# fx3_a.net
KiCad netlist of a schematic drawn in Altium Designer
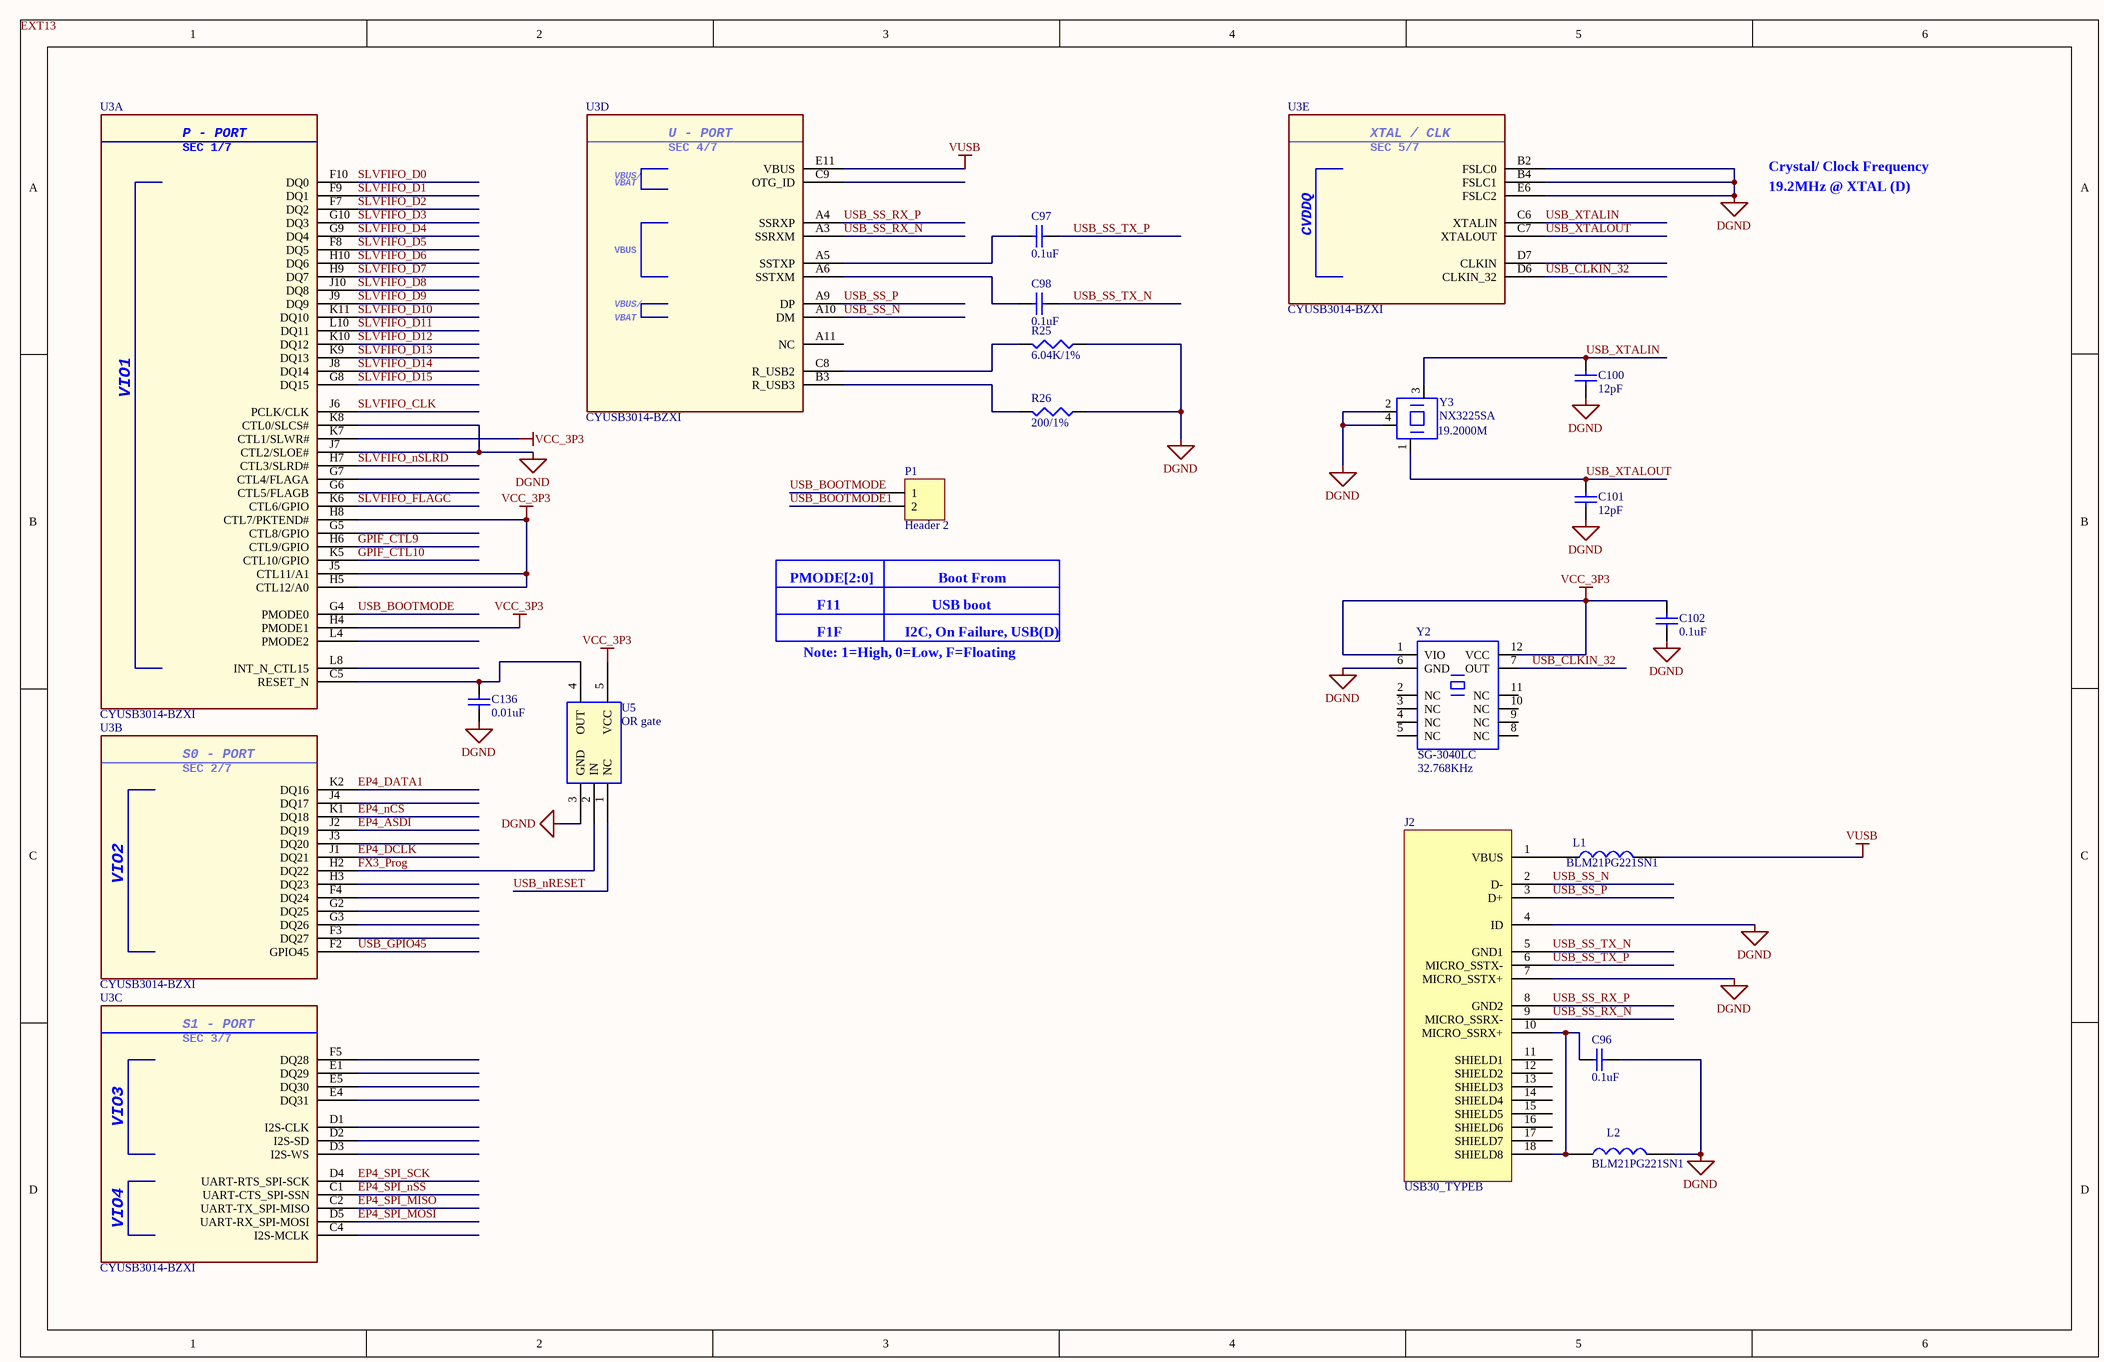
[diagram p0: fx3_a.SchDoc]

(export (version "E")
  (design (tool "Eeschema 10.0.6"))
  (components
    (comp (ref "C96")
      (value "0.1uF")
      (footprint "C_0402")
      (description "Capacitor (Semiconductor SIM Model)")
      (fields (field (name "Comment") "Capacitor") (field (name "PUBLISHER") "Altium Limited"))
      (libsource (lib "Miscellaneous Devices") (part "Cap Semi"))
    )
    (comp (ref "C97")
      (value "0.1uF")
      (footprint "C_0402")
      (description "Capacitor (Semiconductor SIM Model)")
      (fields (field (name "Comment") "Capacitor") (field (name "PUBLISHER") "Altium Limited"))
      (libsource (lib "Miscellaneous Devices") (part "Cap Semi"))
    )
    (comp (ref "C98")
      (value "0.1uF")
      (footprint "C_0402")
      (description "Capacitor (Semiconductor SIM Model)")
      (fields (field (name "Comment") "Capacitor") (field (name "PUBLISHER") "Altium Limited"))
      (libsource (lib "Miscellaneous Devices") (part "Cap Semi"))
    )
    (comp (ref "C100")
      (value "12pF")
      (footprint "C_0402")
      (description "Capacitor (Semiconductor SIM Model)")
      (fields (field (name "Comment") "Capacitor") (field (name "PUBLISHER") "Altium Limited"))
      (libsource (lib "Miscellaneous Devices") (part "Cap Semi"))
    )
    (comp (ref "C101")
      (value "12pF")
      (footprint "C_0402")
      (description "Capacitor (Semiconductor SIM Model)")
      (fields (field (name "Comment") "Capacitor") (field (name "PUBLISHER") "Altium Limited"))
      (libsource (lib "Miscellaneous Devices") (part "Cap Semi"))
    )
    (comp (ref "C102")
      (value "0.1uF")
      (footprint "C_0402")
      (description "Capacitor (Semiconductor SIM Model)")
      (fields (field (name "Comment") "Capacitor") (field (name "PUBLISHER") "Altium Limited"))
      (libsource (lib "Miscellaneous Devices") (part "Cap Semi"))
    )
    (comp (ref "C136")
      (value "0.01uF")
      (footprint "C_0402")
      (description "Capacitor (Semiconductor SIM Model)")
      (fields (field (name "Comment") "Capacitor") (field (name "PUBLISHER") "Altium Limited"))
      (libsource (lib "Miscellaneous Devices") (part "Cap Semi"))
    )
    (comp (ref "J2")
      (value "USB30_TYPEB")
      (footprint "USB3.0 typeB")
      (description "USB30_MICRO_TYPEB")
      (libsource (lib "apex_usb_v2") (part "USB30_TYPEB"))
    )
    (comp (ref "L1")
      (value "BLM21PG221SN1")
      (footprint "SMD_0805")
      (description "Chip Ferrite Bead")
      (libsource (lib "apex_usb_v2") (part "BLM21PXXX"))
    )
    (comp (ref "L2")
      (value "BLM21PG221SN1")
      (footprint "SMD_0805")
      (description "Chip Ferrite Bead")
      (libsource (lib "apex_usb_v2") (part "BLM21PXXX"))
    )
    (comp (ref "P1")
      (value "Header 2")
      (footprint "HDR1X2")
      (description "Header, 2-Pin")
      (fields (field (name "PUBLISHER") "Altium Limited"))
      (libsource (lib "Miscellaneous Connectors") (part "Header 2"))
    )
    (comp (ref "R25")
      (value "6.04K/1%")
      (footprint "J1-0603")
      (description "Resistor")
      (fields (field (name "PUBLISHER") "Altium Limited"))
      (libsource (lib "Miscellaneous Devices") (part "Res3"))
    )
    (comp (ref "R26")
      (value "200/1%")
      (footprint "J1-0603")
      (description "Resistor")
      (fields (field (name "PUBLISHER") "Altium Limited"))
      (libsource (lib "Miscellaneous Devices") (part "Res3"))
    )
    (comp (ref "U3")
      (value "CYUSB3014-BZXI")
      (footprint "CYP-BZX121")
      (description "FX3 CYUSB3014")
      (libsource (lib "apex_usb_v2") (part "CYUSB30XX"))
    )
    (comp (ref "U5")
      (value "OR gate")
      (footprint "TC7SET08FU")
      (libsource (lib "auxiliarylib1") (part "INVERTER"))
    )
    (comp (ref "Y2")
      (value "SG-3040LC")
      (footprint "SG-3040LC")
      (description "CRYSTAL")
      (fields (field (name "ALTIUM_VALUE") "32.768KHz"))
      (libsource (lib "apex_usb_v2") (part "SG3040"))
    )
    (comp (ref "Y3")
      (value "NX3225SA")
      (footprint "CRYSTAL_SMD_32X25")
      (description "CRYSTAL")
      (fields (field (name "ALTIUM_VALUE") "19.2000M"))
      (libsource (lib "clc_ad_pro") (part "NX3225SA"))
    )
  )
  (nets
    (net (code "1") (name "/EP4_ASDI") (class "Default")
      (node (ref "U3") (pin "J2") (pinfunction "DQ19_J2") (pintype "passive"))
    )
    (net (code "2") (name "/EP4_DATA1") (class "Default")
      (node (ref "U3") (pin "K2") (pinfunction "DQ16_K2") (pintype "passive"))
    )
    (net (code "3") (name "/EP4_DCLK") (class "Default")
      (node (ref "U3") (pin "J1") (pinfunction "DQ21_J1") (pintype "passive"))
    )
    (net (code "4") (name "/EP4_SPI_MISO") (class "Default")
      (node (ref "U3") (pin "C2") (pinfunction "UART-TX_SPI-MISO_C2") (pintype "passive"))
    )
    (net (code "5") (name "/EP4_SPI_MOSI") (class "Default")
      (node (ref "U3") (pin "D5") (pinfunction "UART-RX_SPI-MOSI_D5") (pintype "passive"))
    )
    (net (code "6") (name "/EP4_SPI_SCK") (class "Default")
      (node (ref "U3") (pin "D4") (pinfunction "UART-RTS_SPI-SCK_D4") (pintype "passive"))
    )
    (net (code "7") (name "/EP4_SPI_nSS") (class "Default")
      (node (ref "U3") (pin "C1") (pinfunction "UART-CTS_SPI-SSN_C1") (pintype "passive"))
    )
    (net (code "8") (name "/EP4_nCS") (class "Default")
      (node (ref "U3") (pin "K1") (pinfunction "DQ18_K1") (pintype "passive"))
    )
    (net (code "10") (name "/FX3_Prog") (class "Default")
      (node (ref "U3") (pin "H2") (pinfunction "DQ22_H2") (pintype "passive"))
      (node (ref "U5") (pin "2") (pinfunction "IN_2") (pintype "passive"))
    )
    (net (code "11") (name "/GPIF_CTL9") (class "Default")
      (node (ref "U3") (pin "H6") (pinfunction "CTL9/GPIO_H6") (pintype "passive"))
    )
    (net (code "12") (name "/GPIF_CTL10") (class "Default")
      (node (ref "U3") (pin "K5") (pinfunction "CTL10/GPIO_K5") (pintype "passive"))
    )
    (net (code "13") (name "/SLVFIFO_CLK") (class "Default")
      (node (ref "U3") (pin "J6") (pinfunction "PCLK/CLK_J6") (pintype "passive"))
    )
    (net (code "14") (name "/SLVFIFO_D0") (class "Default")
      (node (ref "U3") (pin "F10") (pinfunction "DQ0_F10") (pintype "passive"))
    )
    (net (code "15") (name "/SLVFIFO_D1") (class "Default")
      (node (ref "U3") (pin "F9") (pinfunction "DQ1_F9") (pintype "passive"))
    )
    (net (code "16") (name "/SLVFIFO_D2") (class "Default")
      (node (ref "U3") (pin "F7") (pinfunction "DQ2_F7") (pintype "passive"))
    )
    (net (code "17") (name "/SLVFIFO_D3") (class "Default")
      (node (ref "U3") (pin "G10") (pinfunction "DQ3_G10") (pintype "passive"))
    )
    (net (code "18") (name "/SLVFIFO_D4") (class "Default")
      (node (ref "U3") (pin "G9") (pinfunction "DQ4_G9") (pintype "passive"))
    )
    (net (code "19") (name "/SLVFIFO_D5") (class "Default")
      (node (ref "U3") (pin "F8") (pinfunction "DQ5_F8") (pintype "passive"))
    )
    (net (code "20") (name "/SLVFIFO_D6") (class "Default")
      (node (ref "U3") (pin "H10") (pinfunction "DQ6_H10") (pintype "passive"))
    )
    (net (code "21") (name "/SLVFIFO_D7") (class "Default")
      (node (ref "U3") (pin "H9") (pinfunction "DQ7_H9") (pintype "passive"))
    )
    (net (code "22") (name "/SLVFIFO_D8") (class "Default")
      (node (ref "U3") (pin "J10") (pinfunction "DQ8_J10") (pintype "passive"))
    )
    (net (code "23") (name "/SLVFIFO_D9") (class "Default")
      (node (ref "U3") (pin "J9") (pinfunction "DQ9_J9") (pintype "passive"))
    )
    (net (code "24") (name "/SLVFIFO_D10") (class "Default")
      (node (ref "U3") (pin "K11") (pinfunction "DQ10_K11") (pintype "passive"))
    )
    (net (code "25") (name "/SLVFIFO_D11") (class "Default")
      (node (ref "U3") (pin "L10") (pinfunction "DQ11_L10") (pintype "passive"))
    )
    (net (code "26") (name "/SLVFIFO_D12") (class "Default")
      (node (ref "U3") (pin "K10") (pinfunction "DQ12_K10") (pintype "passive"))
    )
    (net (code "27") (name "/SLVFIFO_D13") (class "Default")
      (node (ref "U3") (pin "K9") (pinfunction "DQ13_K9") (pintype "passive"))
    )
    (net (code "28") (name "/SLVFIFO_D14") (class "Default")
      (node (ref "U3") (pin "J8") (pinfunction "DQ14_J8") (pintype "passive"))
    )
    (net (code "29") (name "/SLVFIFO_D15") (class "Default")
      (node (ref "U3") (pin "G8") (pinfunction "DQ15_G8") (pintype "passive"))
    )
    (net (code "30") (name "/SLVFIFO_FLAGC") (class "Default")
      (node (ref "U3") (pin "K6") (pinfunction "CTL6/GPIO_K6") (pintype "passive"))
    )
    (net (code "31") (name "/SLVFIFO_nSLRD") (class "Default")
      (node (ref "U3") (pin "H7") (pinfunction "CTL3/SLRD#_H7") (pintype "passive"))
    )
    (net (code "32") (name "/USB_BOOTMODE") (class "Default")
      (node (ref "P1") (pin "1") (pinfunction "1_1") (pintype "passive"))
      (node (ref "U3") (pin "G4") (pinfunction "PMODE0_G4") (pintype "passive"))
    )
    (net (code "33") (name "/USB_BOOTMODE1") (class "Default")
      (node (ref "P1") (pin "2") (pinfunction "2_2") (pintype "passive"))
    )
    (net (code "34") (name "/USB_CLKIN_32") (class "Default")
      (node (ref "U3") (pin "D6") (pinfunction "CLKIN_32_D6") (pintype "passive"))
      (node (ref "Y2") (pin "7") (pinfunction "OUT_7") (pintype "passive"))
    )
    (net (code "35") (name "/USB_GPIO45") (class "Default")
      (node (ref "U3") (pin "F2") (pinfunction "GPIO45_F2") (pintype "passive"))
    )
    (net (code "36") (name "/USB_SS_N") (class "Default")
      (node (ref "J2") (pin "2") (pinfunction "D-_2") (pintype "passive"))
      (node (ref "U3") (pin "A10") (pinfunction "DM_A10") (pintype "passive"))
    )
    (net (code "37") (name "/USB_SS_P") (class "Default")
      (node (ref "J2") (pin "3") (pinfunction "D+_3") (pintype "passive"))
      (node (ref "U3") (pin "A9") (pinfunction "DP_A9") (pintype "passive"))
    )
    (net (code "38") (name "/USB_SS_RX_N") (class "Default")
      (node (ref "J2") (pin "9") (pinfunction "MICRO_SSRX-_9") (pintype "passive"))
      (node (ref "U3") (pin "A3") (pinfunction "SSRXM_A3") (pintype "passive"))
    )
    (net (code "39") (name "/USB_SS_RX_P") (class "Default")
      (node (ref "J2") (pin "8") (pinfunction "GND2_8") (pintype "passive"))
      (node (ref "U3") (pin "A4") (pinfunction "SSRXP_A4") (pintype "passive"))
    )
    (net (code "40") (name "/USB_SS_TX_N") (class "Default")
      (node (ref "C98") (pin "2") (pinfunction "2_2") (pintype "passive"))
      (node (ref "J2") (pin "5") (pinfunction "GND1_5") (pintype "passive"))
    )
    (net (code "41") (name "/USB_SS_TX_P") (class "Default")
      (node (ref "C97") (pin "2") (pinfunction "2_2") (pintype "passive"))
      (node (ref "J2") (pin "6") (pinfunction "MICRO_SSTX-_6") (pintype "passive"))
    )
    (net (code "42") (name "/USB_XTALIN") (class "Default")
      (node (ref "C100") (pin "2") (pinfunction "2_2") (pintype "passive"))
      (node (ref "U3") (pin "C6") (pinfunction "XTALIN_C6") (pintype "passive"))
      (node (ref "Y3") (pin "3") (pinfunction "3_3") (pintype "passive"))
    )
    (net (code "43") (name "/USB_XTALOUT") (class "Default")
      (node (ref "C101") (pin "2") (pinfunction "2_2") (pintype "passive"))
      (node (ref "U3") (pin "C7") (pinfunction "XTALOUT_C7") (pintype "passive"))
      (node (ref "Y3") (pin "1") (pinfunction "1_1") (pintype "passive"))
    )
    (net (code "44") (name "/USB_nRESET") (class "Default")
      (node (ref "U5") (pin "1") (pinfunction "NC_1") (pintype "passive"))
    )
    (net (code "45") (name "DGND") (class "Default")
      (node (ref "C100") (pin "1") (pinfunction "1_1") (pintype "passive"))
      (node (ref "C101") (pin "1") (pinfunction "1_1") (pintype "passive"))
      (node (ref "C102") (pin "1") (pinfunction "1_1") (pintype "passive"))
      (node (ref "C136") (pin "2") (pinfunction "2_2") (pintype "passive"))
      (node (ref "C96") (pin "2") (pinfunction "2_2") (pintype "passive"))
      (node (ref "J2") (pin "4") (pinfunction "ID_4") (pintype "passive"))
      (node (ref "J2") (pin "7") (pinfunction "MICRO_SSTX+_7") (pintype "passive"))
      (node (ref "L2") (pin "2") (pinfunction "2_2") (pintype "passive"))
      (node (ref "R25") (pin "1") (pinfunction "1_1") (pintype "passive"))
      (node (ref "R26") (pin "1") (pinfunction "1_1") (pintype "passive"))
      (node (ref "U3") (pin "B2") (pinfunction "FSLC0_B2") (pintype "passive"))
      (node (ref "U3") (pin "B4") (pinfunction "FSLC1_B4") (pintype "passive"))
      (node (ref "U3") (pin "E6") (pinfunction "FSLC2_E6") (pintype "passive"))
      (node (ref "U3") (pin "J7") (pinfunction "CTL2/SLOE#_J7") (pintype "passive"))
      (node (ref "U3") (pin "K8") (pinfunction "CTL0/SLCS#_K8") (pintype "passive"))
      (node (ref "U5") (pin "3") (pinfunction "GND_3") (pintype "passive"))
      (node (ref "Y2") (pin "6") (pinfunction "GND_6") (pintype "passive"))
      (node (ref "Y3") (pin "2") (pinfunction "2_2") (pintype "passive"))
      (node (ref "Y3") (pin "4") (pinfunction "4_4") (pintype "passive"))
    )
    (net (code "46") (name "Net-(J2-MICRO_SSRX+)") (class "Default")
      (node (ref "C96") (pin "1") (pinfunction "1_1") (pintype "passive"))
      (node (ref "J2") (pin "10") (pinfunction "MICRO_SSRX+_10") (pintype "passive"))
      (node (ref "J2") (pin "18") (pinfunction "SHIELD8_18") (pintype "passive"))
      (node (ref "L2") (pin "1") (pinfunction "1_1") (pintype "passive"))
    )
    (net (code "47") (name "Net-(J2-VBUS)") (class "Default")
      (node (ref "J2") (pin "1") (pinfunction "VBUS_1") (pintype "passive"))
      (node (ref "L1") (pin "1") (pinfunction "1_1") (pintype "passive"))
    )
    (net (code "48") (name "Net-(U3A-RESET_N)") (class "Default")
      (node (ref "C136") (pin "1") (pinfunction "1_1") (pintype "passive"))
      (node (ref "U3") (pin "C5") (pinfunction "RESET_N_C5") (pintype "passive"))
      (node (ref "U5") (pin "4") (pinfunction "OUT_4") (pintype "passive"))
    )
    (net (code "49") (name "Net-(U3D-R_USB2)") (class "Default")
      (node (ref "R25") (pin "2") (pinfunction "2_2") (pintype "passive"))
      (node (ref "U3") (pin "C8") (pinfunction "R_USB2_C8") (pintype "passive"))
    )
    (net (code "50") (name "Net-(U3D-R_USB3)") (class "Default")
      (node (ref "R26") (pin "2") (pinfunction "2_2") (pintype "passive"))
      (node (ref "U3") (pin "B3") (pinfunction "R_USB3_B3") (pintype "passive"))
    )
    (net (code "51") (name "Net-(U3D-SSTXM)") (class "Default")
      (node (ref "C98") (pin "1") (pinfunction "1_1") (pintype "passive"))
      (node (ref "U3") (pin "A6") (pinfunction "SSTXM_A6") (pintype "passive"))
    )
    (net (code "52") (name "Net-(U3D-SSTXP)") (class "Default")
      (node (ref "C97") (pin "1") (pinfunction "1_1") (pintype "passive"))
      (node (ref "U3") (pin "A5") (pinfunction "SSTXP_A5") (pintype "passive"))
    )
    (net (code "53") (name "VCC_3P3") (class "Default")
      (node (ref "C102") (pin "2") (pinfunction "2_2") (pintype "passive"))
      (node (ref "U3") (pin "H4") (pinfunction "PMODE1_H4") (pintype "passive"))
      (node (ref "U3") (pin "H5") (pinfunction "CTL12/A0_H5") (pintype "passive"))
      (node (ref "U3") (pin "H8") (pinfunction "CTL7/PKTEND#_H8") (pintype "passive"))
      (node (ref "U3") (pin "J5") (pinfunction "CTL11/A1_J5") (pintype "passive"))
      (node (ref "U3") (pin "K7") (pinfunction "CTL1/SLWR#_K7") (pintype "passive"))
      (node (ref "U5") (pin "5") (pinfunction "VCC_5") (pintype "passive"))
      (node (ref "Y2") (pin "1") (pinfunction "VIO_1") (pintype "passive"))
      (node (ref "Y2") (pin "12") (pinfunction "VCC_12") (pintype "passive"))
    )
    (net (code "54") (name "VUSB") (class "Default")
      (node (ref "L1") (pin "2") (pinfunction "2_2") (pintype "passive"))
      (node (ref "U3") (pin "E11") (pinfunction "VBUS_E11") (pintype "passive"))
    )
    (net (code "55") (name "unconnected-(J2-SHIELD1-Pad11)") (class "Default")
      (node (ref "J2") (pin "11") (pinfunction "SHIELD1_11") (pintype "passive"))
    )
    (net (code "56") (name "unconnected-(J2-SHIELD2-Pad12)") (class "Default")
      (node (ref "J2") (pin "12") (pinfunction "SHIELD2_12") (pintype "passive"))
    )
    (net (code "57") (name "unconnected-(J2-SHIELD3-Pad13)") (class "Default")
      (node (ref "J2") (pin "13") (pinfunction "SHIELD3_13") (pintype "passive"))
    )
    (net (code "58") (name "unconnected-(J2-SHIELD4-Pad14)") (class "Default")
      (node (ref "J2") (pin "14") (pinfunction "SHIELD4_14") (pintype "passive"))
    )
    (net (code "59") (name "unconnected-(J2-SHIELD5-Pad15)") (class "Default")
      (node (ref "J2") (pin "15") (pinfunction "SHIELD5_15") (pintype "passive"))
    )
    (net (code "60") (name "unconnected-(J2-SHIELD6-Pad16)") (class "Default")
      (node (ref "J2") (pin "16") (pinfunction "SHIELD6_16") (pintype "passive"))
    )
    (net (code "61") (name "unconnected-(J2-SHIELD7-Pad17)") (class "Default")
      (node (ref "J2") (pin "17") (pinfunction "SHIELD7_17") (pintype "passive"))
    )
    (net (code "62") (name "unconnected-(U3A-CTL4{slash}FLAGA-PadG7)") (class "Default")
      (node (ref "U3") (pin "G7") (pinfunction "CTL4/FLAGA_G7") (pintype "passive"))
    )
    (net (code "63") (name "unconnected-(U3A-CTL5{slash}FLAGB-PadG6)") (class "Default")
      (node (ref "U3") (pin "G6") (pinfunction "CTL5/FLAGB_G6") (pintype "passive"))
    )
    (net (code "64") (name "unconnected-(U3A-CTL8{slash}GPIO-PadG5)") (class "Default")
      (node (ref "U3") (pin "G5") (pinfunction "CTL8/GPIO_G5") (pintype "passive"))
    )
    (net (code "65") (name "unconnected-(U3A-INT_N_CTL15-PadL8)") (class "Default")
      (node (ref "U3") (pin "L8") (pinfunction "INT_N_CTL15_L8") (pintype "passive"))
    )
    (net (code "66") (name "unconnected-(U3A-PMODE2-PadL4)") (class "Default")
      (node (ref "U3") (pin "L4") (pinfunction "PMODE2_L4") (pintype "passive"))
    )
    (net (code "67") (name "unconnected-(U3B-DQ17-PadJ4)") (class "Default")
      (node (ref "U3") (pin "J4") (pinfunction "DQ17_J4") (pintype "passive"))
    )
    (net (code "68") (name "unconnected-(U3B-DQ20-PadJ3)") (class "Default")
      (node (ref "U3") (pin "J3") (pinfunction "DQ20_J3") (pintype "passive"))
    )
    (net (code "69") (name "unconnected-(U3B-DQ23-PadH3)") (class "Default")
      (node (ref "U3") (pin "H3") (pinfunction "DQ23_H3") (pintype "passive"))
    )
    (net (code "70") (name "unconnected-(U3B-DQ24-PadF4)") (class "Default")
      (node (ref "U3") (pin "F4") (pinfunction "DQ24_F4") (pintype "passive"))
    )
    (net (code "71") (name "unconnected-(U3B-DQ25-PadG2)") (class "Default")
      (node (ref "U3") (pin "G2") (pinfunction "DQ25_G2") (pintype "passive"))
    )
    (net (code "72") (name "unconnected-(U3B-DQ26-PadG3)") (class "Default")
      (node (ref "U3") (pin "G3") (pinfunction "DQ26_G3") (pintype "passive"))
    )
    (net (code "73") (name "unconnected-(U3B-DQ27-PadF3)") (class "Default")
      (node (ref "U3") (pin "F3") (pinfunction "DQ27_F3") (pintype "passive"))
    )
    (net (code "74") (name "unconnected-(U3C-DQ28-PadF5)") (class "Default")
      (node (ref "U3") (pin "F5") (pinfunction "DQ28_F5") (pintype "passive"))
    )
    (net (code "75") (name "unconnected-(U3C-DQ29-PadE1)") (class "Default")
      (node (ref "U3") (pin "E1") (pinfunction "DQ29_E1") (pintype "passive"))
    )
    (net (code "76") (name "unconnected-(U3C-DQ30-PadE5)") (class "Default")
      (node (ref "U3") (pin "E5") (pinfunction "DQ30_E5") (pintype "passive"))
    )
    (net (code "77") (name "unconnected-(U3C-DQ31-PadE4)") (class "Default")
      (node (ref "U3") (pin "E4") (pinfunction "DQ31_E4") (pintype "passive"))
    )
    (net (code "78") (name "unconnected-(U3C-I2S-CLK-PadD1)") (class "Default")
      (node (ref "U3") (pin "D1") (pinfunction "I2S-CLK_D1") (pintype "passive"))
    )
    (net (code "79") (name "unconnected-(U3C-I2S-MCLK-PadC4)") (class "Default")
      (node (ref "U3") (pin "C4") (pinfunction "I2S-MCLK_C4") (pintype "passive"))
    )
    (net (code "80") (name "unconnected-(U3C-I2S-SD-PadD2)") (class "Default")
      (node (ref "U3") (pin "D2") (pinfunction "I2S-SD_D2") (pintype "passive"))
    )
    (net (code "81") (name "unconnected-(U3C-I2S-WS-PadD3)") (class "Default")
      (node (ref "U3") (pin "D3") (pinfunction "I2S-WS_D3") (pintype "passive"))
    )
    (net (code "82") (name "unconnected-(U3D-NC-PadA11)") (class "Default")
      (node (ref "U3") (pin "A11") (pinfunction "NC_A11") (pintype "passive"))
    )
    (net (code "83") (name "unconnected-(U3D-OTG_ID-PadC9)") (class "Default")
      (node (ref "U3") (pin "C9") (pinfunction "OTG_ID_C9") (pintype "passive"))
    )
    (net (code "84") (name "unconnected-(U3E-CLKIN-PadD7)") (class "Default")
      (node (ref "U3") (pin "D7") (pinfunction "CLKIN_D7") (pintype "passive"))
    )
    (net (code "85") (name "unconnected-(Y2-NC-Pad2)") (class "Default")
      (node (ref "Y2") (pin "2") (pinfunction "NC_2") (pintype "passive"))
    )
    (net (code "86") (name "unconnected-(Y2-NC-Pad3)") (class "Default")
      (node (ref "Y2") (pin "3") (pinfunction "NC_3") (pintype "passive"))
    )
    (net (code "87") (name "unconnected-(Y2-NC-Pad4)") (class "Default")
      (node (ref "Y2") (pin "4") (pinfunction "NC_4") (pintype "passive"))
    )
    (net (code "88") (name "unconnected-(Y2-NC-Pad5)") (class "Default")
      (node (ref "Y2") (pin "5") (pinfunction "NC_5") (pintype "passive"))
    )
    (net (code "89") (name "unconnected-(Y2-NC-Pad8)") (class "Default")
      (node (ref "Y2") (pin "8") (pinfunction "NC_8") (pintype "passive"))
    )
    (net (code "90") (name "unconnected-(Y2-NC-Pad9)") (class "Default")
      (node (ref "Y2") (pin "9") (pinfunction "NC_9") (pintype "passive"))
    )
    (net (code "91") (name "unconnected-(Y2-NC-Pad10)") (class "Default")
      (node (ref "Y2") (pin "10") (pinfunction "NC_10") (pintype "passive"))
    )
    (net (code "92") (name "unconnected-(Y2-NC-Pad11)") (class "Default")
      (node (ref "Y2") (pin "11") (pinfunction "NC_11") (pintype "passive"))
    )
  )
)
